# MucDuino_Cherry.net
KiCad netlist of a schematic drawn in EAGLE
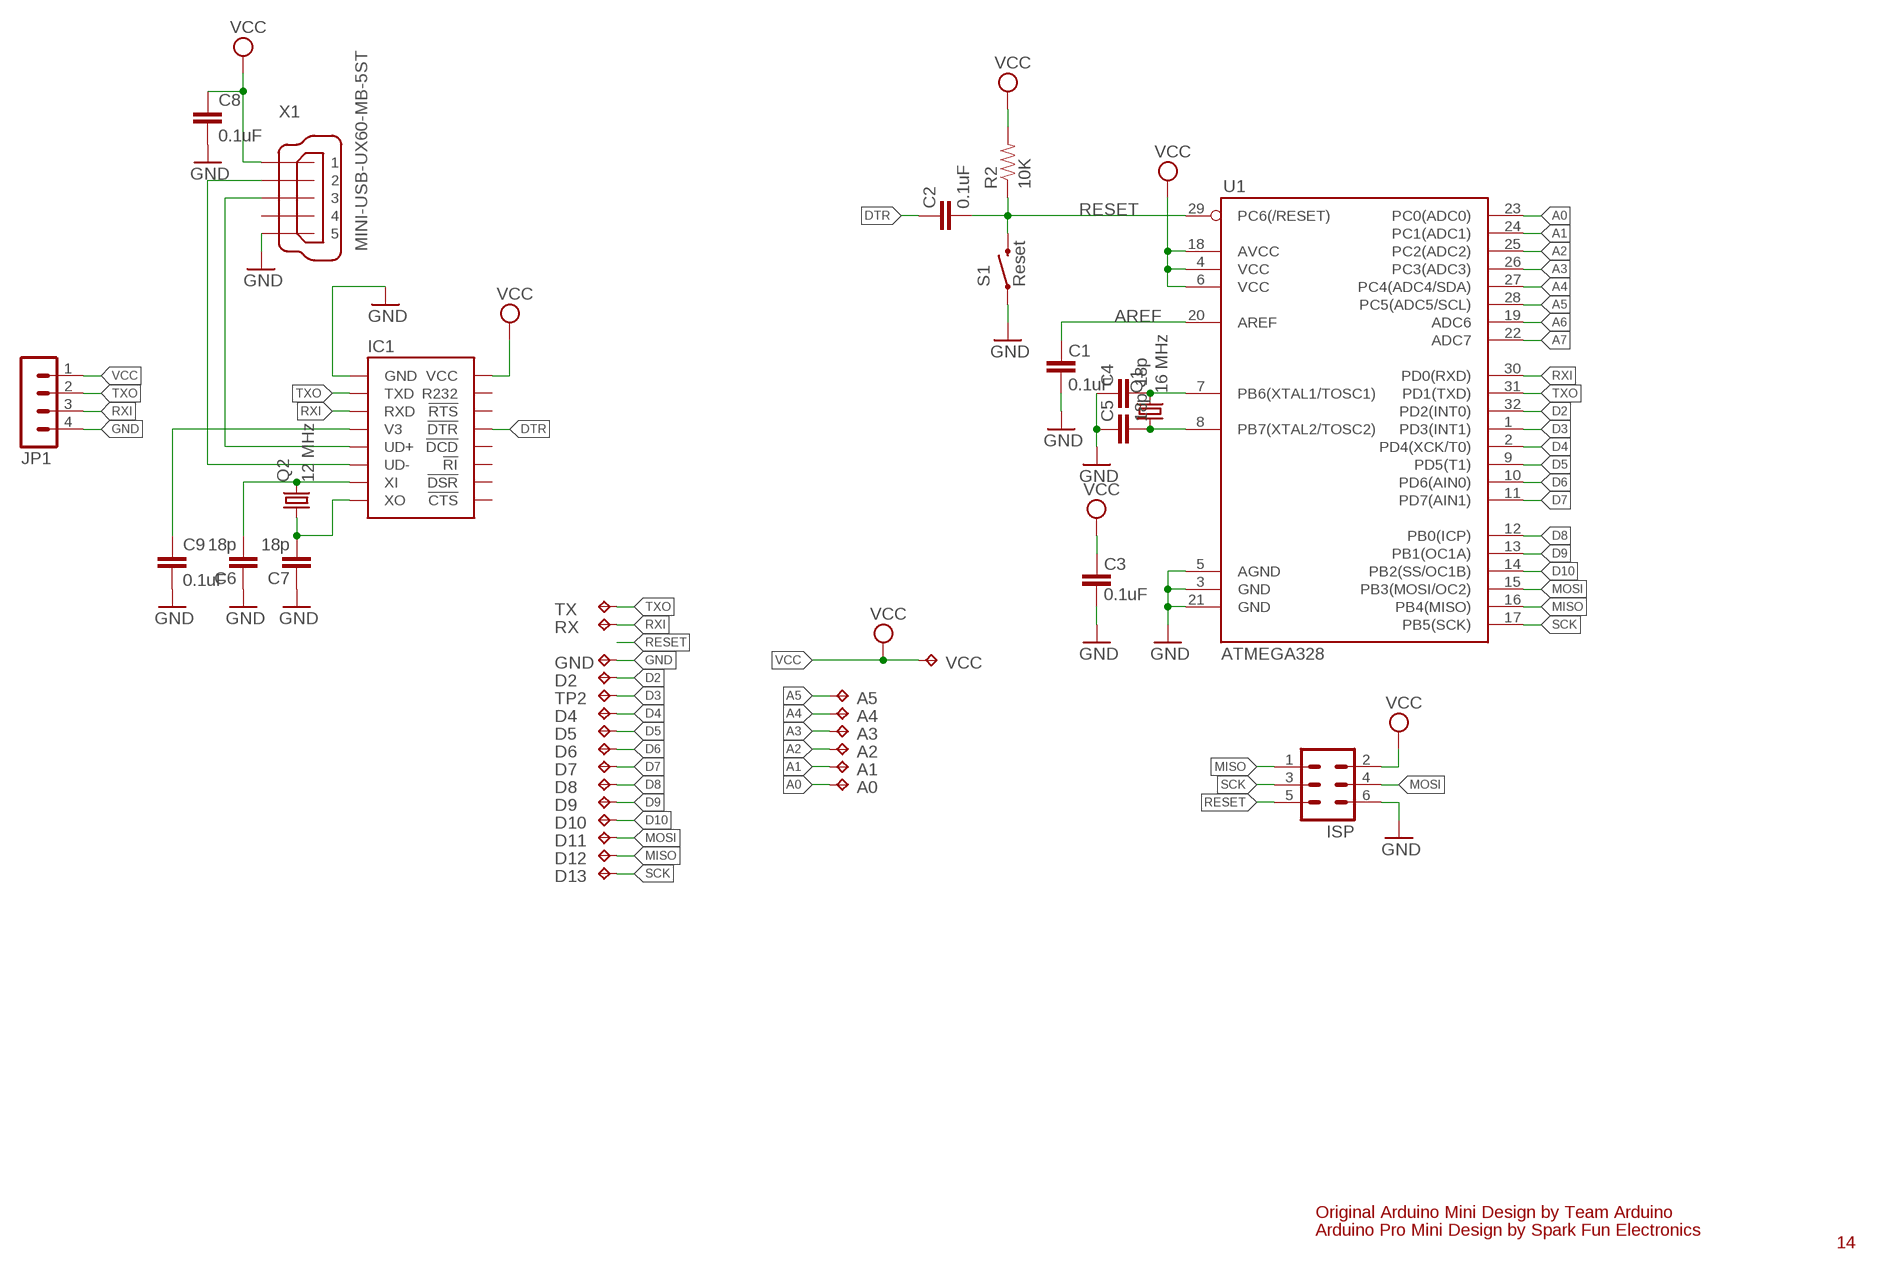
[diagram p0: schematic, sheet 1]

(export (version "E")
  (design (tool "Eeschema 10.0.6"))
  (components
    (comp (ref "A0")
      (value "TPPAD1-13")
      (footprint "eagle-import:P1-13")
      (libsource (lib "eagle-import") (part "TPPAD1-13"))
    )
    (comp (ref "A1")
      (value "TPPAD1-13")
      (footprint "eagle-import:P1-13")
      (libsource (lib "eagle-import") (part "TPPAD1-13"))
    )
    (comp (ref "A2")
      (value "TPPAD1-13")
      (footprint "eagle-import:P1-13")
      (libsource (lib "eagle-import") (part "TPPAD1-13"))
    )
    (comp (ref "A3")
      (value "TPPAD1-13")
      (footprint "eagle-import:P1-13")
      (libsource (lib "eagle-import") (part "TPPAD1-13"))
    )
    (comp (ref "A4")
      (value "TPPAD1-13")
      (footprint "eagle-import:P1-13")
      (libsource (lib "eagle-import") (part "TPPAD1-13"))
    )
    (comp (ref "A5")
      (value "TPPAD1-13")
      (footprint "eagle-import:P1-13")
      (libsource (lib "eagle-import") (part "TPPAD1-13"))
    )
    (comp (ref "C1")
      (value "0.1uF")
      (footprint "eagle-import:0603-CAP")
      (libsource (lib "eagle-import") (part "CAP0603-CAP"))
    )
    (comp (ref "C2")
      (value "0.1uF")
      (footprint "eagle-import:0603-CAP")
      (libsource (lib "eagle-import") (part "CAP0603-CAP"))
    )
    (comp (ref "C3")
      (value "0.1uF")
      (footprint "eagle-import:0603-CAP")
      (libsource (lib "eagle-import") (part "CAP0603-CAP"))
    )
    (comp (ref "C4")
      (value "18p")
      (footprint "eagle-import:0603-CAP")
      (libsource (lib "eagle-import") (part "CAP0603-CAP"))
    )
    (comp (ref "C5")
      (value "18p")
      (footprint "eagle-import:0603-CAP")
      (libsource (lib "eagle-import") (part "CAP0603-CAP"))
    )
    (comp (ref "C6")
      (value "18p")
      (footprint "eagle-import:0603-CAP")
      (libsource (lib "eagle-import") (part "CAP0603-CAP"))
    )
    (comp (ref "C7")
      (value "18p")
      (footprint "eagle-import:0603-CAP")
      (libsource (lib "eagle-import") (part "CAP0603-CAP"))
    )
    (comp (ref "C8")
      (value "0.1uF")
      (footprint "eagle-import:0603-CAP")
      (libsource (lib "eagle-import") (part "CAP0603-CAP"))
    )
    (comp (ref "C9")
      (value "0.1uF")
      (footprint "eagle-import:0603-CAP")
      (libsource (lib "eagle-import") (part "CAP0603-CAP"))
    )
    (comp (ref "D2")
      (value "TPPAD1-13")
      (footprint "eagle-import:P1-13")
      (libsource (lib "eagle-import") (part "TPPAD1-13"))
    )
    (comp (ref "D4")
      (value "TPPAD1-13")
      (footprint "eagle-import:P1-13")
      (libsource (lib "eagle-import") (part "TPPAD1-13"))
    )
    (comp (ref "D5")
      (value "TPPAD1-13")
      (footprint "eagle-import:P1-13")
      (libsource (lib "eagle-import") (part "TPPAD1-13"))
    )
    (comp (ref "D6")
      (value "TPPAD1-13")
      (footprint "eagle-import:P1-13")
      (libsource (lib "eagle-import") (part "TPPAD1-13"))
    )
    (comp (ref "D7")
      (value "TPPAD1-13")
      (footprint "eagle-import:P1-13")
      (libsource (lib "eagle-import") (part "TPPAD1-13"))
    )
    (comp (ref "D8")
      (value "TPPAD1-13")
      (footprint "eagle-import:P1-13")
      (libsource (lib "eagle-import") (part "TPPAD1-13"))
    )
    (comp (ref "D9")
      (value "TPPAD1-13")
      (footprint "eagle-import:P1-13")
      (libsource (lib "eagle-import") (part "TPPAD1-13"))
    )
    (comp (ref "D10")
      (value "TPPAD1-13")
      (footprint "eagle-import:P1-13")
      (libsource (lib "eagle-import") (part "TPPAD1-13"))
    )
    (comp (ref "D11")
      (value "TPPAD1-13")
      (footprint "eagle-import:P1-13")
      (libsource (lib "eagle-import") (part "TPPAD1-13"))
    )
    (comp (ref "D12")
      (value "TPPAD1-13")
      (footprint "eagle-import:P1-13")
      (libsource (lib "eagle-import") (part "TPPAD1-13"))
    )
    (comp (ref "D13")
      (value "TPPAD1-13")
      (footprint "eagle-import:P1-13")
      (libsource (lib "eagle-import") (part "TPPAD1-13"))
    )
    (comp (ref "GND")
      (value "TPPAD1-13")
      (footprint "eagle-import:P1-13")
      (libsource (lib "eagle-import") (part "TPPAD1-13"))
    )
    (comp (ref "IC1")
      (value "CH340G")
      (footprint "eagle-import:SOP16-209MM")
      (libsource (lib "eagle-import") (part "CH340G"))
    )
    (comp (ref "ISP")
      (value "MA03-2")
      (footprint "eagle-import:MA03-2")
      (libsource (lib "eagle-import") (part "MA03-2"))
    )
    (comp (ref "JP1")
      (value "MA04-1")
      (footprint "eagle-import:MA04-1")
      (libsource (lib "eagle-import") (part "MA04-1"))
    )
    (comp (ref "Q1")
      (value "16 MHz")
      (footprint "eagle-import:HC49UP")
      (libsource (lib "eagle-import") (part "CRYSTALHC49UP"))
    )
    (comp (ref "Q2")
      (value "12 MHz")
      (footprint "eagle-import:HC49UP")
      (libsource (lib "eagle-import") (part "CRYSTALHC49UP"))
    )
    (comp (ref "R2")
      (value "10K")
      (footprint "eagle-import:0603-RES")
      (libsource (lib "eagle-import") (part "RESISTOR0603-RES"))
    )
    (comp (ref "RX")
      (value "TPPAD1-13")
      (footprint "eagle-import:P1-13")
      (libsource (lib "eagle-import") (part "TPPAD1-13"))
    )
    (comp (ref "S1")
      (value "Reset")
      (footprint "eagle-import:TACTILE-SWITCH-SMD-ALT01")
      (libsource (lib "eagle-import") (part "SWITCH-MOMENTARY-2SMD-ALT01"))
    )
    (comp (ref "TP2")
      (value "TPPAD1-13")
      (footprint "eagle-import:P1-13")
      (libsource (lib "eagle-import") (part "TPPAD1-13"))
    )
    (comp (ref "TX")
      (value "TPPAD1-13")
      (footprint "eagle-import:P1-13")
      (libsource (lib "eagle-import") (part "TPPAD1-13"))
    )
    (comp (ref "U1")
      (value "ATMEGA328")
      (footprint "eagle-import:TQFP32-08")
      (libsource (lib "eagle-import") (part "ATMEGA168"))
    )
    (comp (ref "VCC")
      (value "TPPAD1-13")
      (footprint "eagle-import:P1-13")
      (libsource (lib "eagle-import") (part "TPPAD1-13"))
    )
    (comp (ref "X1")
      (value "MINI-USB-UX60-MB-5ST")
      (footprint "eagle-import:UX60-MB-5ST")
      (libsource (lib "eagle-import") (part "MINI-USB-UX60-MB-5ST"))
    )
  )
  (nets
    (net (code "1") (name "/AREF") (class "Default")
      (node (ref "C1") (pin "2") (pinfunction "2_2") (pintype "passive"))
      (node (ref "U1") (pin "20") (pinfunction "AREF_20") (pintype "bidirectional"))
    )
    (net (code "2") (name "A0") (class "Default")
      (node (ref "A0") (pin "TP") (pinfunction "TP_TP") (pintype "input"))
      (node (ref "U1") (pin "23") (pinfunction "PC0(ADC0)_23") (pintype "bidirectional"))
    )
    (net (code "3") (name "A1") (class "Default")
      (node (ref "A1") (pin "TP") (pinfunction "TP_TP") (pintype "input"))
      (node (ref "U1") (pin "24") (pinfunction "PC1(ADC1)_24") (pintype "bidirectional"))
    )
    (net (code "4") (name "A2") (class "Default")
      (node (ref "A2") (pin "TP") (pinfunction "TP_TP") (pintype "input"))
      (node (ref "U1") (pin "25") (pinfunction "PC2(ADC2)_25") (pintype "bidirectional"))
    )
    (net (code "5") (name "A3") (class "Default")
      (node (ref "A3") (pin "TP") (pinfunction "TP_TP") (pintype "input"))
      (node (ref "U1") (pin "26") (pinfunction "PC3(ADC3)_26") (pintype "bidirectional"))
    )
    (net (code "6") (name "A4") (class "Default")
      (node (ref "A4") (pin "TP") (pinfunction "TP_TP") (pintype "input"))
      (node (ref "U1") (pin "27") (pinfunction "PC4(ADC4/SDA)_27") (pintype "bidirectional"))
    )
    (net (code "7") (name "A5") (class "Default")
      (node (ref "A5") (pin "TP") (pinfunction "TP_TP") (pintype "input"))
      (node (ref "U1") (pin "28") (pinfunction "PC5(ADC5/SCL)_28") (pintype "bidirectional"))
    )
    (net (code "8") (name "A6") (class "Default")
      (node (ref "U1") (pin "19") (pinfunction "ADC6_19") (pintype "bidirectional"))
    )
    (net (code "9") (name "A7") (class "Default")
      (node (ref "U1") (pin "22") (pinfunction "ADC7_22") (pintype "bidirectional"))
    )
    (net (code "10") (name "D2") (class "Default")
      (node (ref "D2") (pin "TP") (pinfunction "TP_TP") (pintype "input"))
      (node (ref "U1") (pin "32") (pinfunction "PD2(INT0)_32") (pintype "bidirectional"))
    )
    (net (code "11") (name "D3") (class "Default")
      (node (ref "TP2") (pin "TP") (pinfunction "TP_TP") (pintype "input"))
      (node (ref "U1") (pin "1") (pinfunction "PD3(INT1)_1") (pintype "bidirectional"))
    )
    (net (code "12") (name "D4") (class "Default")
      (node (ref "D4") (pin "TP") (pinfunction "TP_TP") (pintype "input"))
      (node (ref "U1") (pin "2") (pinfunction "PD4(XCK/T0)_2") (pintype "bidirectional"))
    )
    (net (code "13") (name "D5") (class "Default")
      (node (ref "D5") (pin "TP") (pinfunction "TP_TP") (pintype "input"))
      (node (ref "U1") (pin "9") (pinfunction "PD5(T1)_9") (pintype "bidirectional"))
    )
    (net (code "14") (name "D6") (class "Default")
      (node (ref "D6") (pin "TP") (pinfunction "TP_TP") (pintype "input"))
      (node (ref "U1") (pin "10") (pinfunction "PD6(AIN0)_10") (pintype "bidirectional"))
    )
    (net (code "15") (name "D7") (class "Default")
      (node (ref "D7") (pin "TP") (pinfunction "TP_TP") (pintype "input"))
      (node (ref "U1") (pin "11") (pinfunction "PD7(AIN1)_11") (pintype "bidirectional"))
    )
    (net (code "16") (name "D8") (class "Default")
      (node (ref "D8") (pin "TP") (pinfunction "TP_TP") (pintype "input"))
      (node (ref "U1") (pin "12") (pinfunction "PB0(ICP)_12") (pintype "bidirectional"))
    )
    (net (code "17") (name "D9") (class "Default")
      (node (ref "D9") (pin "TP") (pinfunction "TP_TP") (pintype "input"))
      (node (ref "U1") (pin "13") (pinfunction "PB1(OC1A)_13") (pintype "bidirectional"))
    )
    (net (code "18") (name "D10") (class "Default")
      (node (ref "D10") (pin "TP") (pinfunction "TP_TP") (pintype "input"))
      (node (ref "U1") (pin "14") (pinfunction "PB2(SS/OC1B)_14") (pintype "bidirectional"))
    )
    (net (code "19") (name "DTR") (class "Default")
      (node (ref "C2") (pin "2") (pinfunction "2_2") (pintype "passive"))
      (node (ref "IC1") (pin "P$13") (pinfunction "~{DTR}_P$13") (pintype "bidirectional"))
    )
    (net (code "20") (name "GND") (class "Default")
      (node (ref "C1") (pin "1") (pinfunction "1_1") (pintype "passive"))
      (node (ref "C3") (pin "1") (pinfunction "1_1") (pintype "passive"))
      (node (ref "C4") (pin "2") (pinfunction "2_2") (pintype "passive"))
      (node (ref "C5") (pin "2") (pinfunction "2_2") (pintype "passive"))
      (node (ref "C6") (pin "2") (pinfunction "2_2") (pintype "passive"))
      (node (ref "C7") (pin "2") (pinfunction "2_2") (pintype "passive"))
      (node (ref "C8") (pin "2") (pinfunction "2_2") (pintype "passive"))
      (node (ref "C9") (pin "2") (pinfunction "2_2") (pintype "passive"))
      (node (ref "GND") (pin "TP") (pinfunction "TP_TP") (pintype "input"))
      (node (ref "IC1") (pin "P$1") (pinfunction "GND_P$1") (pintype "bidirectional"))
      (node (ref "ISP") (pin "6") (pinfunction "6_6") (pintype "passive"))
      (node (ref "JP1") (pin "4") (pinfunction "4_4") (pintype "passive"))
      (node (ref "S1") (pin "1") (pinfunction "1_1") (pintype "passive"))
      (node (ref "S1") (pin "2") (pinfunction "1_2") (pintype "passive"))
      (node (ref "U1") (pin "21") (pinfunction "GND_21") (pintype "bidirectional"))
      (node (ref "U1") (pin "3") (pinfunction "GND_3") (pintype "bidirectional"))
      (node (ref "U1") (pin "5") (pinfunction "AGND_5") (pintype "bidirectional"))
      (node (ref "X1") (pin "5") (pinfunction "5_5") (pintype "input"))
    )
    (net (code "21") (name "MISO") (class "Default")
      (node (ref "D12") (pin "TP") (pinfunction "TP_TP") (pintype "input"))
      (node (ref "ISP") (pin "1") (pinfunction "1_1") (pintype "passive"))
      (node (ref "U1") (pin "16") (pinfunction "PB4(MISO)_16") (pintype "bidirectional"))
    )
    (net (code "22") (name "MOSI") (class "Default")
      (node (ref "D11") (pin "TP") (pinfunction "TP_TP") (pintype "input"))
      (node (ref "ISP") (pin "4") (pinfunction "4_4") (pintype "passive"))
      (node (ref "U1") (pin "15") (pinfunction "PB3(MOSI/OC2)_15") (pintype "bidirectional"))
    )
    (net (code "23") (name "Net-(IC1-UD+)") (class "Default")
      (node (ref "IC1") (pin "P$5") (pinfunction "UD+_P$5") (pintype "bidirectional"))
      (node (ref "X1") (pin "3") (pinfunction "3_3") (pintype "input"))
    )
    (net (code "24") (name "Net-(IC1-UD-)") (class "Default")
      (node (ref "IC1") (pin "P$6") (pinfunction "UD-_P$6") (pintype "bidirectional"))
      (node (ref "X1") (pin "2") (pinfunction "2_2") (pintype "input"))
    )
    (net (code "25") (name "Net-(IC1-V3)") (class "Default")
      (node (ref "C9") (pin "1") (pinfunction "1_1") (pintype "passive"))
      (node (ref "IC1") (pin "P$4") (pinfunction "V3_P$4") (pintype "bidirectional"))
    )
    (net (code "26") (name "Net-(IC1-XI)") (class "Default")
      (node (ref "C6") (pin "1") (pinfunction "1_1") (pintype "passive"))
      (node (ref "IC1") (pin "P$7") (pinfunction "XI_P$7") (pintype "bidirectional"))
      (node (ref "Q2") (pin "2") (pinfunction "2_2") (pintype "passive"))
    )
    (net (code "27") (name "Net-(IC1-XO)") (class "Default")
      (node (ref "C7") (pin "1") (pinfunction "1_1") (pintype "passive"))
      (node (ref "IC1") (pin "P$8") (pinfunction "XO_P$8") (pintype "bidirectional"))
      (node (ref "Q2") (pin "1") (pinfunction "1_1") (pintype "passive"))
    )
    (net (code "28") (name "Net-(U1-PB6(XTAL1{slash}TOSC1))") (class "Default")
      (node (ref "C4") (pin "1") (pinfunction "1_1") (pintype "passive"))
      (node (ref "Q1") (pin "2") (pinfunction "2_2") (pintype "passive"))
      (node (ref "U1") (pin "7") (pinfunction "PB6(XTAL1/TOSC1)_7") (pintype "bidirectional"))
    )
    (net (code "29") (name "Net-(U1-PB7(XTAL2{slash}TOSC2))") (class "Default")
      (node (ref "C5") (pin "1") (pinfunction "1_1") (pintype "passive"))
      (node (ref "Q1") (pin "1") (pinfunction "1_1") (pintype "passive"))
      (node (ref "U1") (pin "8") (pinfunction "PB7(XTAL2/TOSC2)_8") (pintype "bidirectional"))
    )
    (net (code "30") (name "RESET") (class "Default")
      (node (ref "C2") (pin "1") (pinfunction "1_1") (pintype "passive"))
      (node (ref "ISP") (pin "5") (pinfunction "5_5") (pintype "passive"))
      (node (ref "R2") (pin "1") (pinfunction "1_1") (pintype "passive"))
      (node (ref "S1") (pin "3") (pinfunction "2_3") (pintype "passive"))
      (node (ref "S1") (pin "4") (pinfunction "2_4") (pintype "passive"))
      (node (ref "U1") (pin "29") (pinfunction "PC6(/RESET)_29") (pintype "bidirectional"))
    )
    (net (code "31") (name "RXI") (class "Default")
      (node (ref "IC1") (pin "P$3") (pinfunction "RXD_P$3") (pintype "bidirectional"))
      (node (ref "JP1") (pin "3") (pinfunction "3_3") (pintype "passive"))
      (node (ref "RX") (pin "TP") (pinfunction "TP_TP") (pintype "input"))
      (node (ref "U1") (pin "30") (pinfunction "PD0(RXD)_30") (pintype "bidirectional"))
    )
    (net (code "32") (name "SCK") (class "Default")
      (node (ref "D13") (pin "TP") (pinfunction "TP_TP") (pintype "input"))
      (node (ref "ISP") (pin "3") (pinfunction "3_3") (pintype "passive"))
      (node (ref "U1") (pin "17") (pinfunction "PB5(SCK)_17") (pintype "bidirectional"))
    )
    (net (code "33") (name "TXO") (class "Default")
      (node (ref "IC1") (pin "P$2") (pinfunction "TXD_P$2") (pintype "bidirectional"))
      (node (ref "JP1") (pin "2") (pinfunction "2_2") (pintype "passive"))
      (node (ref "TX") (pin "TP") (pinfunction "TP_TP") (pintype "input"))
      (node (ref "U1") (pin "31") (pinfunction "PD1(TXD)_31") (pintype "bidirectional"))
    )
    (net (code "34") (name "VCC") (class "Default")
      (node (ref "C3") (pin "2") (pinfunction "2_2") (pintype "passive"))
      (node (ref "C8") (pin "1") (pinfunction "1_1") (pintype "passive"))
      (node (ref "IC1") (pin "P$16") (pinfunction "VCC_P$16") (pintype "bidirectional"))
      (node (ref "ISP") (pin "2") (pinfunction "2_2") (pintype "passive"))
      (node (ref "JP1") (pin "1") (pinfunction "1_1") (pintype "passive"))
      (node (ref "R2") (pin "2") (pinfunction "2_2") (pintype "passive"))
      (node (ref "U1") (pin "18") (pinfunction "AVCC_18") (pintype "bidirectional"))
      (node (ref "U1") (pin "4") (pinfunction "VCC_4") (pintype "bidirectional"))
      (node (ref "U1") (pin "6") (pinfunction "VCC_6") (pintype "bidirectional"))
      (node (ref "VCC") (pin "TP") (pinfunction "TP_TP") (pintype "input"))
      (node (ref "X1") (pin "1") (pinfunction "1_1") (pintype "input"))
    )
    (net (code "35") (name "unconnected-(IC1-R232-PadP$15)") (class "Default")
      (node (ref "IC1") (pin "P$15") (pinfunction "R232_P$15") (pintype "bidirectional"))
    )
    (net (code "36") (name "unconnected-(IC1-~{CTS}-PadP$9)") (class "Default")
      (node (ref "IC1") (pin "P$9") (pinfunction "~{CTS}_P$9") (pintype "bidirectional"))
    )
    (net (code "37") (name "unconnected-(IC1-~{DCD}-PadP$12)") (class "Default")
      (node (ref "IC1") (pin "P$12") (pinfunction "~{DCD}_P$12") (pintype "bidirectional"))
    )
    (net (code "38") (name "unconnected-(IC1-~{DSR}-PadP$10)") (class "Default")
      (node (ref "IC1") (pin "P$10") (pinfunction "~{DSR}_P$10") (pintype "bidirectional"))
    )
    (net (code "39") (name "unconnected-(IC1-~{RI}-PadP$11)") (class "Default")
      (node (ref "IC1") (pin "P$11") (pinfunction "~{RI}_P$11") (pintype "bidirectional"))
    )
    (net (code "40") (name "unconnected-(IC1-~{RTS}-PadP$14)") (class "Default")
      (node (ref "IC1") (pin "P$14") (pinfunction "~{RTS}_P$14") (pintype "bidirectional"))
    )
    (net (code "41") (name "unconnected-(X1-Pad4)") (class "Default")
      (node (ref "X1") (pin "4") (pinfunction "4_4") (pintype "input"))
    )
  )
)
